# Battery_Voltage_Detection.net
KiCad netlist of a schematic drawn in Altium Designer
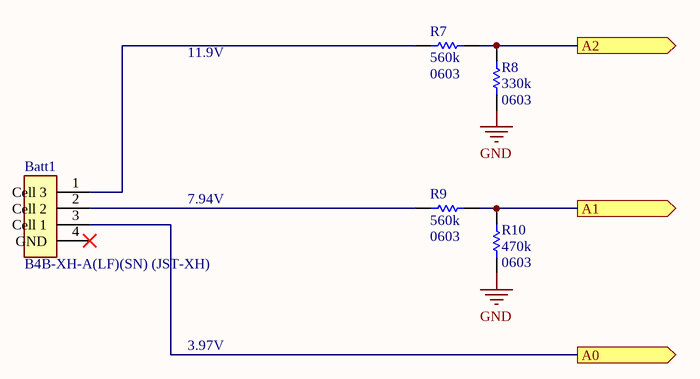
[diagram p0: Battery Voltage Detection.SchDoc]

(export (version "E")
  (design (tool "Eeschema 10.0.6"))
  (components
    (comp (ref "Batt1")
      (value "B4B-XH-A(LF)(SN) (JST-XH)")
      (footprint "JST_B4B-XH-A(LF)(SN)")
      (description "Connector Header Through Hole 4 position 0.098 _2.50mm_")
      (fields (field (name "MP") "B4B-XH-A_LF__SN_") (field (name "MF") "JST Sales"))
      (libsource (lib "B4B-XH-A_LF__SN_") (part "B4B-XH-A(LF)(SN)"))
    )
    (comp (ref "R7")
      (value "560k")
      (footprint "SMD-0603-RES")
      (description "Resistor")
      (fields (field (name "ALTIUM_VALUE") "0603") (field (name "PUBLISHER") "Altium Limited"))
      (libsource (lib "Miscellaneous Devices") (part "Res1"))
    )
    (comp (ref "R8")
      (value "330k")
      (footprint "SMD-0603-RES")
      (description "Resistor")
      (fields (field (name "ALTIUM_VALUE") "0603") (field (name "PUBLISHER") "Altium Limited"))
      (libsource (lib "Miscellaneous Devices") (part "Res1"))
    )
    (comp (ref "R9")
      (value "560k")
      (footprint "SMD-0603-RES")
      (description "Resistor")
      (fields (field (name "ALTIUM_VALUE") "0603") (field (name "PUBLISHER") "Altium Limited"))
      (libsource (lib "Miscellaneous Devices") (part "Res1"))
    )
    (comp (ref "R10")
      (value "470k")
      (footprint "SMD-0603-RES")
      (description "Resistor")
      (fields (field (name "ALTIUM_VALUE") "0603") (field (name "PUBLISHER") "Altium Limited"))
      (libsource (lib "Miscellaneous Devices") (part "Res1"))
    )
  )
  (nets
    (net (code "1") (name "/A0") (class "Default")
      (node (ref "Batt1") (pin "3") (pinfunction "Cell_1_3") (pintype "passive"))
    )
    (net (code "2") (name "/A1") (class "Default")
      (node (ref "R10") (pin "2") (pinfunction "2_2") (pintype "passive"))
      (node (ref "R9") (pin "1") (pinfunction "1_1") (pintype "passive"))
    )
    (net (code "3") (name "/A2") (class "Default")
      (node (ref "R7") (pin "1") (pinfunction "1_1") (pintype "passive"))
      (node (ref "R8") (pin "2") (pinfunction "2_2") (pintype "passive"))
    )
    (net (code "4") (name "GND") (class "Default")
      (node (ref "R10") (pin "1") (pinfunction "1_1") (pintype "passive"))
      (node (ref "R8") (pin "1") (pinfunction "1_1") (pintype "passive"))
    )
    (net (code "5") (name "Net-(Batt1-Cell_2)") (class "Default")
      (node (ref "Batt1") (pin "2") (pinfunction "Cell_2_2") (pintype "passive"))
      (node (ref "R9") (pin "2") (pinfunction "2_2") (pintype "passive"))
    )
    (net (code "6") (name "Net-(Batt1-Cell_3)") (class "Default")
      (node (ref "Batt1") (pin "1") (pinfunction "Cell_3_1") (pintype "passive"))
      (node (ref "R7") (pin "2") (pinfunction "2_2") (pintype "passive"))
    )
    (net (code "7") (name "unconnected-(Batt1-GND-Pad4)") (class "Default")
      (node (ref "Batt1") (pin "4") (pinfunction "GND_4") (pintype "passive+no_connect"))
    )
  )
)
